# Pressure-Sensor.net
KiCad netlist of a schematic drawn in Altium Designer
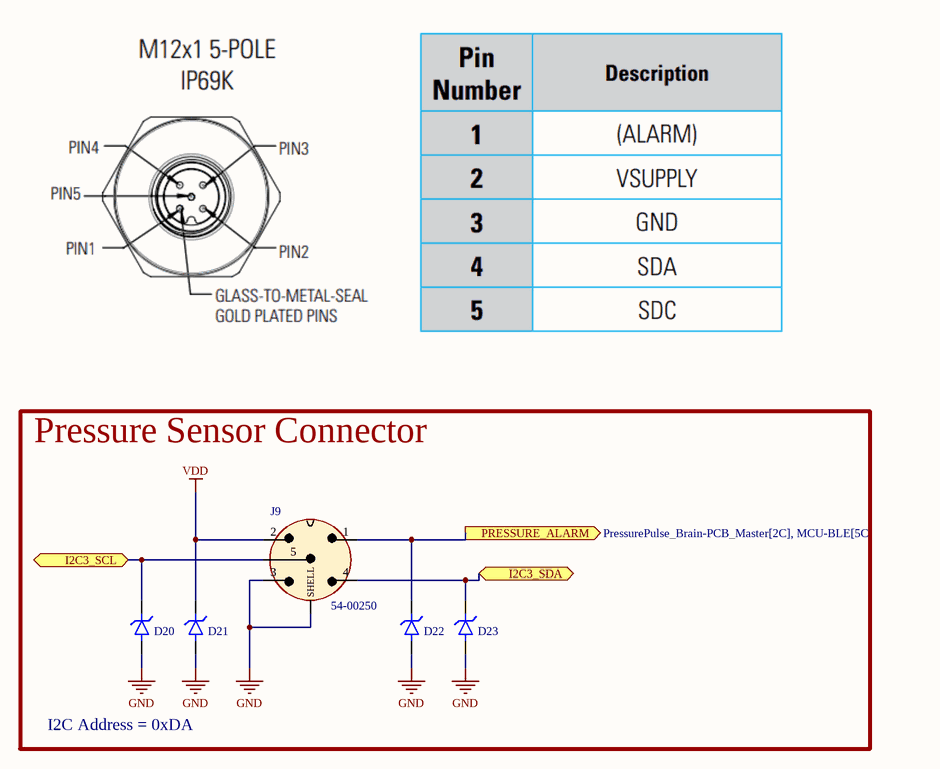
[diagram p0: Pressure-Sensor.SchDoc]

(export (version "E")
  (design (tool "Eeschema 10.0.6"))
  (components
    (comp (ref "D20")
      (value "RCLAMP0521P.TCT")
      (footprint "PressurePulse:BDFN2C051V40")
      (description "25V Clamp 4A (8/20µs) Ipp Tvs Diode Surface Mount SLP1006P2")
      (fields (field (name "MFR") "BORN"))
      (libsource (lib "PressurePulse") (part "TVS DIODE"))
    )
    (comp (ref "D21")
      (value "RCLAMP0521P.TCT")
      (footprint "PressurePulse:BDFN2C051V40")
      (description "25V Clamp 4A (8/20µs) Ipp Tvs Diode Surface Mount SLP1006P2")
      (fields (field (name "MFR") "BORN"))
      (libsource (lib "PressurePulse") (part "TVS DIODE"))
    )
    (comp (ref "D22")
      (value "RCLAMP0521P.TCT")
      (footprint "PressurePulse:BDFN2C051V40")
      (description "25V Clamp 4A (8/20µs) Ipp Tvs Diode Surface Mount SLP1006P2")
      (fields (field (name "MFR") "BORN"))
      (libsource (lib "PressurePulse") (part "TVS DIODE"))
    )
    (comp (ref "D23")
      (value "RCLAMP0521P.TCT")
      (footprint "PressurePulse:BDFN2C051V40")
      (description "25V Clamp 4A (8/20µs) Ipp Tvs Diode Surface Mount SLP1006P2")
      (fields (field (name "MFR") "BORN"))
      (libsource (lib "PressurePulse") (part "TVS DIODE"))
    )
    (comp (ref "J9")
      (value "54-00250")
      (footprint "PressurePulse:TENSILITY_54-00250")
      (description "CONN PLUG MALE 5POS GOLD SOLDER")
      (fields (field (name "MFR") "Tensility International Corp"))
      (libsource (lib "PressurePulse") (part "M12 5POS TH RA"))
    )
  )
  (nets
    (net (code "1") (name "/I2C3_SCL") (class "Default")
      (node (ref "D20") (pin "K") (pinfunction "K_K") (pintype "passive"))
      (node (ref "J9") (pin "5") (pinfunction "5_5") (pintype "passive"))
    )
    (net (code "2") (name "/I2C3_SDA") (class "Default")
      (node (ref "D23") (pin "K") (pinfunction "K_K") (pintype "passive"))
      (node (ref "J9") (pin "4") (pinfunction "4_4") (pintype "passive"))
    )
    (net (code "3") (name "/PRESSURE_ALARM") (class "Default")
      (node (ref "D22") (pin "K") (pinfunction "K_K") (pintype "passive"))
      (node (ref "J9") (pin "1") (pinfunction "1_1") (pintype "passive"))
    )
    (net (code "4") (name "GND") (class "Default")
      (node (ref "D20") (pin "A") (pinfunction "A_A") (pintype "passive"))
      (node (ref "D21") (pin "A") (pinfunction "A_A") (pintype "passive"))
      (node (ref "D22") (pin "A") (pinfunction "A_A") (pintype "passive"))
      (node (ref "D23") (pin "A") (pinfunction "A_A") (pintype "passive"))
      (node (ref "J9") (pin "3") (pinfunction "3_3") (pintype "passive"))
      (node (ref "J9") (pin "SHELL") (pinfunction "SHELL_SHELL") (pintype "passive"))
    )
    (net (code "5") (name "VDD") (class "Default")
      (node (ref "D21") (pin "K") (pinfunction "K_K") (pintype "passive"))
      (node (ref "J9") (pin "2") (pinfunction "2_2") (pintype "passive"))
    )
  )
)
